# open-race-scale-load-amp.net
KiCad netlist of a schematic drawn in EAGLE
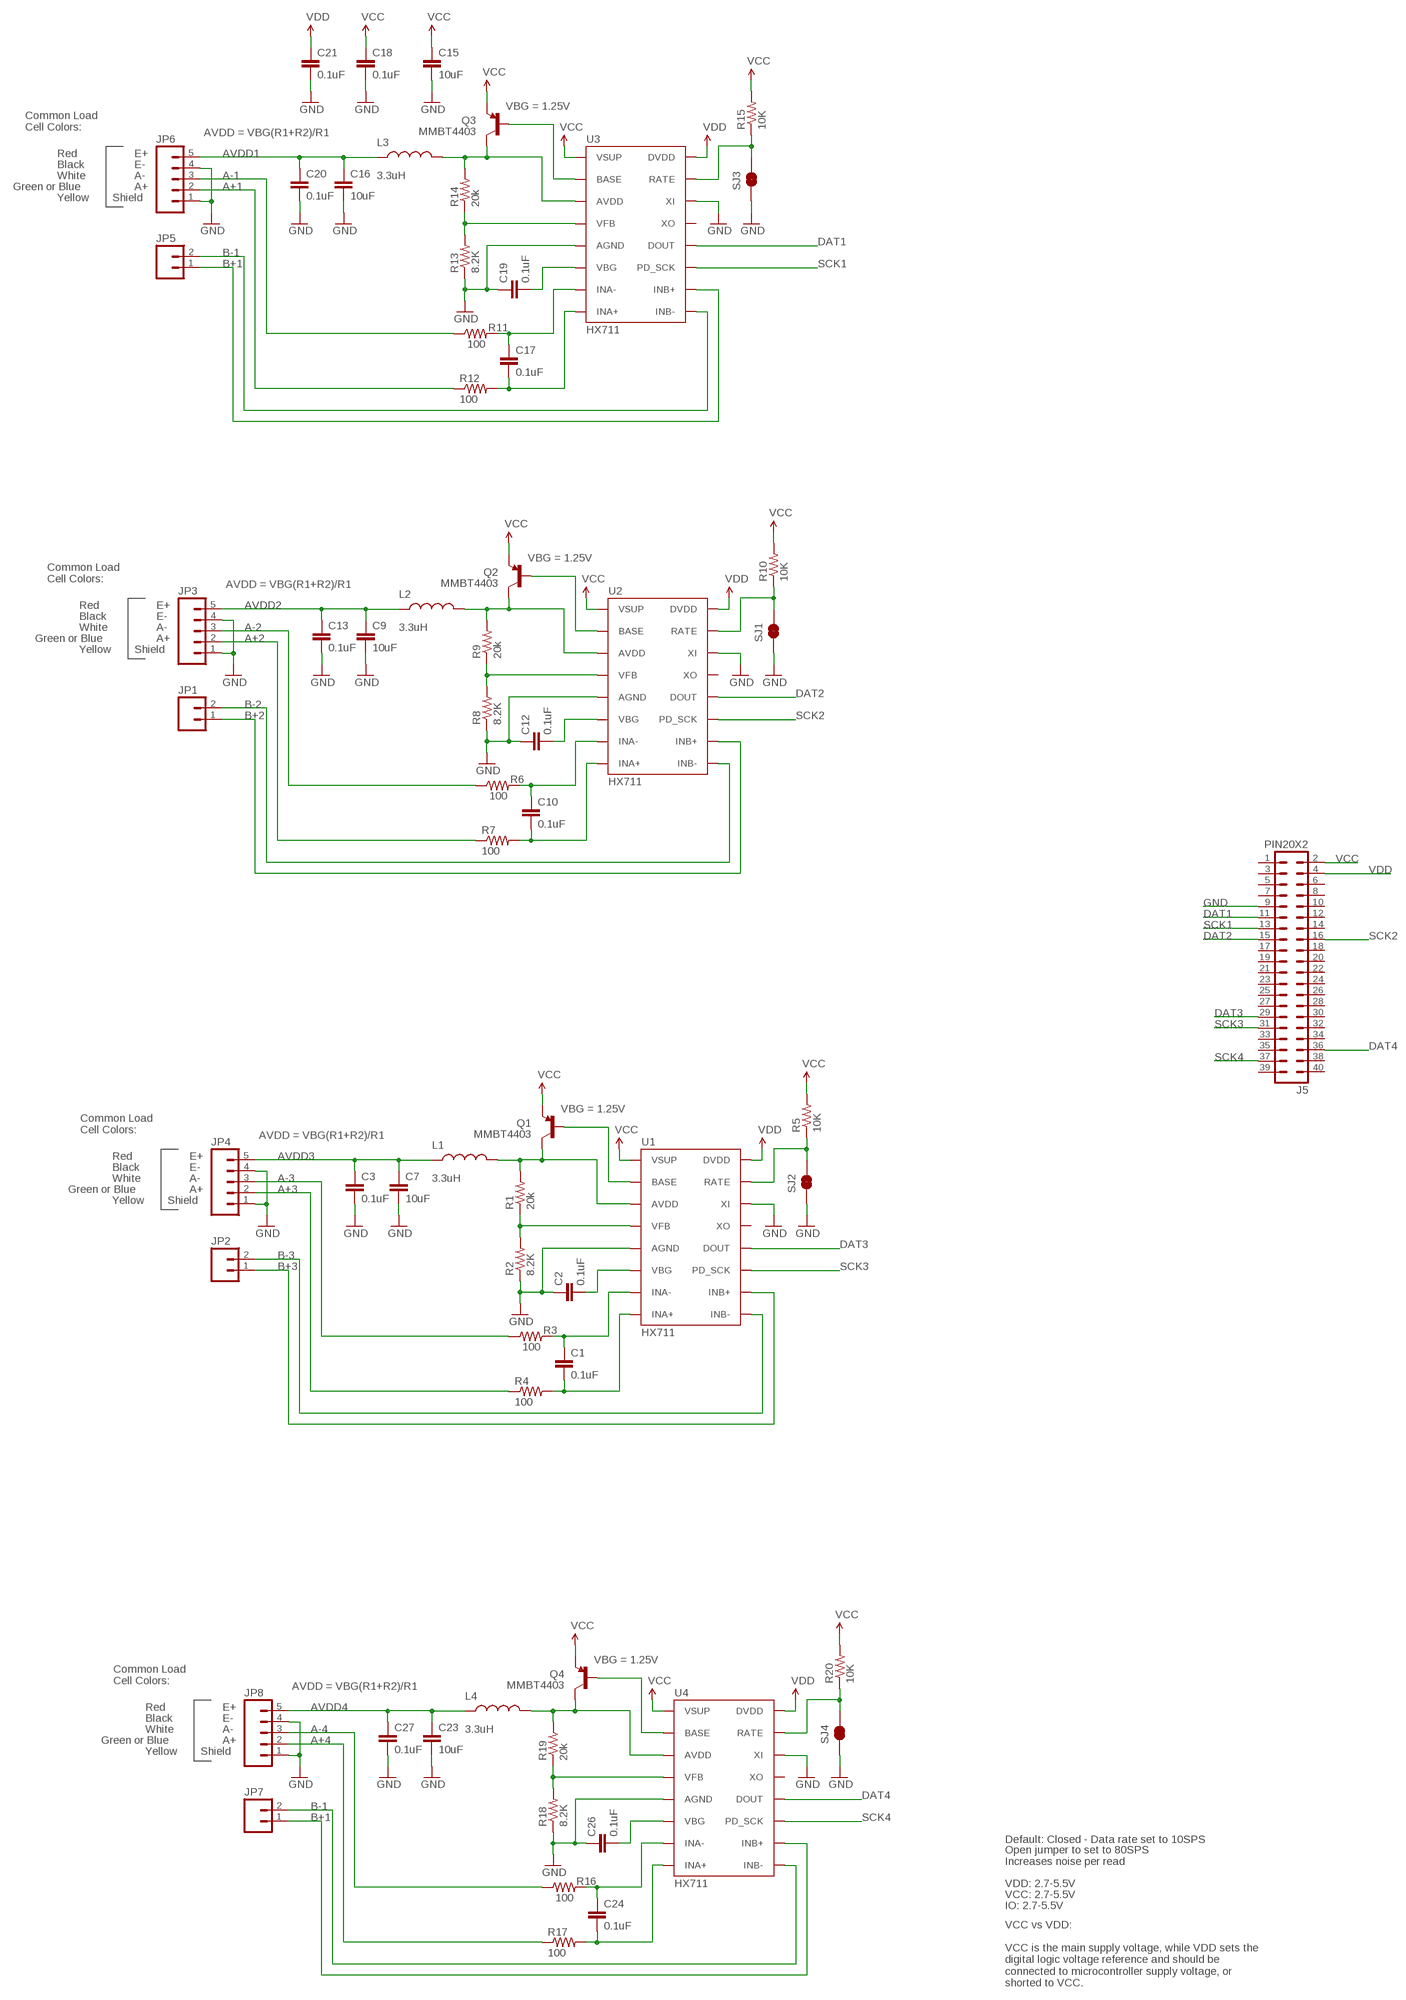
[diagram p0: schematic, sheet 1]

(export (version "E")
  (design (tool "Eeschema 10.0.6"))
  (components
    (comp (ref "C1")
      (value "0.1uF")
      (footprint "eagle-import:0603-CAP")
      (libsource (lib "eagle-import") (part "0.1UF-25V-5%(0603)"))
    )
    (comp (ref "C2")
      (value "0.1uF")
      (footprint "eagle-import:0603-CAP")
      (libsource (lib "eagle-import") (part "0.1UF-25V-5%(0603)"))
    )
    (comp (ref "C3")
      (value "0.1uF")
      (footprint "eagle-import:0603-CAP")
      (libsource (lib "eagle-import") (part "0.1UF-25V-5%(0603)"))
    )
    (comp (ref "C7")
      (value "10uF")
      (footprint "eagle-import:1210")
      (libsource (lib "eagle-import") (part "10UF50V20%(1210)"))
    )
    (comp (ref "C9")
      (value "10uF")
      (footprint "eagle-import:1210")
      (libsource (lib "eagle-import") (part "10UF50V20%(1210)"))
    )
    (comp (ref "C10")
      (value "0.1uF")
      (footprint "eagle-import:0603-CAP")
      (libsource (lib "eagle-import") (part "0.1UF-25V-5%(0603)"))
    )
    (comp (ref "C12")
      (value "0.1uF")
      (footprint "eagle-import:0603-CAP")
      (libsource (lib "eagle-import") (part "0.1UF-25V-5%(0603)"))
    )
    (comp (ref "C13")
      (value "0.1uF")
      (footprint "eagle-import:0603-CAP")
      (libsource (lib "eagle-import") (part "0.1UF-25V-5%(0603)"))
    )
    (comp (ref "C15")
      (value "10uF")
      (footprint "eagle-import:1210")
      (libsource (lib "eagle-import") (part "10UF50V20%(1210)"))
    )
    (comp (ref "C16")
      (value "10uF")
      (footprint "eagle-import:1210")
      (libsource (lib "eagle-import") (part "10UF50V20%(1210)"))
    )
    (comp (ref "C17")
      (value "0.1uF")
      (footprint "eagle-import:0603-CAP")
      (libsource (lib "eagle-import") (part "0.1UF-25V-5%(0603)"))
    )
    (comp (ref "C18")
      (value "0.1uF")
      (footprint "eagle-import:0603-CAP")
      (libsource (lib "eagle-import") (part "0.1UF-25V-5%(0603)"))
    )
    (comp (ref "C19")
      (value "0.1uF")
      (footprint "eagle-import:0603-CAP")
      (libsource (lib "eagle-import") (part "0.1UF-25V-5%(0603)"))
    )
    (comp (ref "C20")
      (value "0.1uF")
      (footprint "eagle-import:0603-CAP")
      (libsource (lib "eagle-import") (part "0.1UF-25V-5%(0603)"))
    )
    (comp (ref "C21")
      (value "0.1uF")
      (footprint "eagle-import:0603-CAP")
      (libsource (lib "eagle-import") (part "0.1UF-25V-5%(0603)"))
    )
    (comp (ref "C23")
      (value "10uF")
      (footprint "eagle-import:1210")
      (libsource (lib "eagle-import") (part "10UF50V20%(1210)"))
    )
    (comp (ref "C24")
      (value "0.1uF")
      (footprint "eagle-import:0603-CAP")
      (libsource (lib "eagle-import") (part "0.1UF-25V-5%(0603)"))
    )
    (comp (ref "C26")
      (value "0.1uF")
      (footprint "eagle-import:0603-CAP")
      (libsource (lib "eagle-import") (part "0.1UF-25V-5%(0603)"))
    )
    (comp (ref "C27")
      (value "0.1uF")
      (footprint "eagle-import:0603-CAP")
      (libsource (lib "eagle-import") (part "0.1UF-25V-5%(0603)"))
    )
    (comp (ref "J5")
      (value "PIN20X2")
      (footprint "eagle-import:PIN_20X2")
      (libsource (lib "eagle-import") (part "PIN20X2"))
    )
    (comp (ref "JP1")
      (value "M02PTH")
      (footprint "eagle-import:1X02")
      (libsource (lib "eagle-import") (part "M02PTH"))
    )
    (comp (ref "JP2")
      (value "M02PTH")
      (footprint "eagle-import:1X02")
      (libsource (lib "eagle-import") (part "M02PTH"))
    )
    (comp (ref "JP3")
      (value "M05PTH")
      (footprint "eagle-import:1X05")
      (libsource (lib "eagle-import") (part "M05PTH"))
    )
    (comp (ref "JP4")
      (value "M05PTH")
      (footprint "eagle-import:1X05")
      (libsource (lib "eagle-import") (part "M05PTH"))
    )
    (comp (ref "JP5")
      (value "M02PTH")
      (footprint "eagle-import:1X02")
      (libsource (lib "eagle-import") (part "M02PTH"))
    )
    (comp (ref "JP6")
      (value "M05PTH")
      (footprint "eagle-import:1X05")
      (libsource (lib "eagle-import") (part "M05PTH"))
    )
    (comp (ref "JP7")
      (value "M02PTH")
      (footprint "eagle-import:1X02")
      (libsource (lib "eagle-import") (part "M02PTH"))
    )
    (comp (ref "JP8")
      (value "M05PTH")
      (footprint "eagle-import:1X05")
      (libsource (lib "eagle-import") (part "M05PTH"))
    )
    (comp (ref "L1")
      (value "3.3uH")
      (footprint "eagle-import:0805")
      (libsource (lib "eagle-import") (part "INDUCTOR0805-IND"))
    )
    (comp (ref "L2")
      (value "3.3uH")
      (footprint "eagle-import:0805")
      (libsource (lib "eagle-import") (part "INDUCTOR0805-IND"))
    )
    (comp (ref "L3")
      (value "3.3uH")
      (footprint "eagle-import:0805")
      (libsource (lib "eagle-import") (part "INDUCTOR0805-IND"))
    )
    (comp (ref "L4")
      (value "3.3uH")
      (footprint "eagle-import:0805")
      (libsource (lib "eagle-import") (part "INDUCTOR0805-IND"))
    )
    (comp (ref "Q1")
      (value "MMBT4403")
      (footprint "eagle-import:SOT23-3")
      (libsource (lib "eagle-import") (part "TRANSISTOR_PNPMMBT4403"))
    )
    (comp (ref "Q2")
      (value "MMBT4403")
      (footprint "eagle-import:SOT23-3")
      (libsource (lib "eagle-import") (part "TRANSISTOR_PNPMMBT4403"))
    )
    (comp (ref "Q3")
      (value "MMBT4403")
      (footprint "eagle-import:SOT23-3")
      (libsource (lib "eagle-import") (part "TRANSISTOR_PNPMMBT4403"))
    )
    (comp (ref "Q4")
      (value "MMBT4403")
      (footprint "eagle-import:SOT23-3")
      (libsource (lib "eagle-import") (part "TRANSISTOR_PNPMMBT4403"))
    )
    (comp (ref "R1")
      (value "20k")
      (footprint "eagle-import:0603-RES")
      (libsource (lib "eagle-import") (part "20KOHM1/10W1%(0603)"))
    )
    (comp (ref "R2")
      (value "8.2K")
      (footprint "eagle-import:0603-RES")
      (libsource (lib "eagle-import") (part "8.2KOHM-1/10W-5%(0603)"))
    )
    (comp (ref "R3")
      (value "100")
      (footprint "eagle-import:0603-RES")
      (libsource (lib "eagle-import") (part "100OHM-1/10W-1%(0603)"))
    )
    (comp (ref "R4")
      (value "100")
      (footprint "eagle-import:0603-RES")
      (libsource (lib "eagle-import") (part "100OHM-1/10W-1%(0603)"))
    )
    (comp (ref "R5")
      (value "10K")
      (footprint "eagle-import:0603-RES")
      (libsource (lib "eagle-import") (part "10KOHM-1/10W-1%(0603)0603"))
    )
    (comp (ref "R6")
      (value "100")
      (footprint "eagle-import:0603-RES")
      (libsource (lib "eagle-import") (part "100OHM-1/10W-1%(0603)"))
    )
    (comp (ref "R7")
      (value "100")
      (footprint "eagle-import:0603-RES")
      (libsource (lib "eagle-import") (part "100OHM-1/10W-1%(0603)"))
    )
    (comp (ref "R8")
      (value "8.2K")
      (footprint "eagle-import:0603-RES")
      (libsource (lib "eagle-import") (part "8.2KOHM-1/10W-5%(0603)"))
    )
    (comp (ref "R9")
      (value "20k")
      (footprint "eagle-import:0603-RES")
      (libsource (lib "eagle-import") (part "20KOHM1/10W1%(0603)"))
    )
    (comp (ref "R10")
      (value "10K")
      (footprint "eagle-import:0603-RES")
      (libsource (lib "eagle-import") (part "10KOHM-1/10W-1%(0603)0603"))
    )
    (comp (ref "R11")
      (value "100")
      (footprint "eagle-import:0603-RES")
      (libsource (lib "eagle-import") (part "100OHM-1/10W-1%(0603)"))
    )
    (comp (ref "R12")
      (value "100")
      (footprint "eagle-import:0603-RES")
      (libsource (lib "eagle-import") (part "100OHM-1/10W-1%(0603)"))
    )
    (comp (ref "R13")
      (value "8.2K")
      (footprint "eagle-import:0603-RES")
      (libsource (lib "eagle-import") (part "8.2KOHM-1/10W-5%(0603)"))
    )
    (comp (ref "R14")
      (value "20k")
      (footprint "eagle-import:0603-RES")
      (libsource (lib "eagle-import") (part "20KOHM1/10W1%(0603)"))
    )
    (comp (ref "R15")
      (value "10K")
      (footprint "eagle-import:0603-RES")
      (libsource (lib "eagle-import") (part "10KOHM-1/10W-1%(0603)0603"))
    )
    (comp (ref "R16")
      (value "100")
      (footprint "eagle-import:0603-RES")
      (libsource (lib "eagle-import") (part "100OHM-1/10W-1%(0603)"))
    )
    (comp (ref "R17")
      (value "100")
      (footprint "eagle-import:0603-RES")
      (libsource (lib "eagle-import") (part "100OHM-1/10W-1%(0603)"))
    )
    (comp (ref "R18")
      (value "8.2K")
      (footprint "eagle-import:0603-RES")
      (libsource (lib "eagle-import") (part "8.2KOHM-1/10W-5%(0603)"))
    )
    (comp (ref "R19")
      (value "20k")
      (footprint "eagle-import:0603-RES")
      (libsource (lib "eagle-import") (part "20KOHM1/10W1%(0603)"))
    )
    (comp (ref "R20")
      (value "10K")
      (footprint "eagle-import:0603-RES")
      (libsource (lib "eagle-import") (part "10KOHM-1/10W-1%(0603)0603"))
    )
    (comp (ref "SJ1")
      (value "JUMPER-PAD-2-NC_BY_TRACE")
      (footprint "eagle-import:PAD-JUMPER-2-NC_BY_TRACE_YES_SILK")
      (libsource (lib "eagle-import") (part "JUMPER-PAD-2-NC_BY_TRACE"))
    )
    (comp (ref "SJ2")
      (value "JUMPER-PAD-2-NC_BY_TRACE")
      (footprint "eagle-import:PAD-JUMPER-2-NC_BY_TRACE_YES_SILK")
      (libsource (lib "eagle-import") (part "JUMPER-PAD-2-NC_BY_TRACE"))
    )
    (comp (ref "SJ3")
      (value "JUMPER-PAD-2-NC_BY_TRACE")
      (footprint "eagle-import:PAD-JUMPER-2-NC_BY_TRACE_YES_SILK")
      (libsource (lib "eagle-import") (part "JUMPER-PAD-2-NC_BY_TRACE"))
    )
    (comp (ref "SJ4")
      (value "JUMPER-PAD-2-NC_BY_TRACE")
      (footprint "eagle-import:PAD-JUMPER-2-NC_BY_TRACE_YES_SILK")
      (libsource (lib "eagle-import") (part "JUMPER-PAD-2-NC_BY_TRACE"))
    )
    (comp (ref "U1")
      (value "HX711")
      (footprint "eagle-import:SO16")
      (libsource (lib "eagle-import") (part "HX711HX711"))
    )
    (comp (ref "U2")
      (value "HX711")
      (footprint "eagle-import:SO16")
      (libsource (lib "eagle-import") (part "HX711HX711"))
    )
    (comp (ref "U3")
      (value "HX711")
      (footprint "eagle-import:SO16")
      (libsource (lib "eagle-import") (part "HX711HX711"))
    )
    (comp (ref "U4")
      (value "HX711")
      (footprint "eagle-import:SO16")
      (libsource (lib "eagle-import") (part "HX711HX711"))
    )
  )
  (nets
    (net (code "1") (name "/A+1") (class "Default")
      (node (ref "JP6") (pin "2") (pinfunction "2_2") (pintype "passive"))
      (node (ref "R12") (pin "1") (pinfunction "1_1") (pintype "passive"))
    )
    (net (code "2") (name "/A+2") (class "Default")
      (node (ref "JP3") (pin "2") (pinfunction "2_2") (pintype "passive"))
      (node (ref "R7") (pin "1") (pinfunction "1_1") (pintype "passive"))
    )
    (net (code "3") (name "/A+3") (class "Default")
      (node (ref "JP4") (pin "2") (pinfunction "2_2") (pintype "passive"))
      (node (ref "R4") (pin "1") (pinfunction "1_1") (pintype "passive"))
    )
    (net (code "4") (name "/A+4") (class "Default")
      (node (ref "JP8") (pin "2") (pinfunction "2_2") (pintype "passive"))
      (node (ref "R17") (pin "1") (pinfunction "1_1") (pintype "passive"))
    )
    (net (code "5") (name "/A-1") (class "Default")
      (node (ref "JP6") (pin "3") (pinfunction "3_3") (pintype "passive"))
      (node (ref "R11") (pin "1") (pinfunction "1_1") (pintype "passive"))
    )
    (net (code "6") (name "/A-2") (class "Default")
      (node (ref "JP3") (pin "3") (pinfunction "3_3") (pintype "passive"))
      (node (ref "R6") (pin "1") (pinfunction "1_1") (pintype "passive"))
    )
    (net (code "7") (name "/A-3") (class "Default")
      (node (ref "JP4") (pin "3") (pinfunction "3_3") (pintype "passive"))
      (node (ref "R3") (pin "1") (pinfunction "1_1") (pintype "passive"))
    )
    (net (code "8") (name "/A-4") (class "Default")
      (node (ref "JP8") (pin "3") (pinfunction "3_3") (pintype "passive"))
      (node (ref "R16") (pin "1") (pinfunction "1_1") (pintype "passive"))
    )
    (net (code "9") (name "/AVDD1") (class "Default")
      (node (ref "C16") (pin "1") (pinfunction "1_1") (pintype "passive"))
      (node (ref "C20") (pin "1") (pinfunction "1_1") (pintype "passive"))
      (node (ref "JP6") (pin "5") (pinfunction "5_5") (pintype "passive"))
      (node (ref "L3") (pin "1") (pinfunction "1_1") (pintype "passive"))
    )
    (net (code "10") (name "/AVDD2") (class "Default")
      (node (ref "C13") (pin "1") (pinfunction "1_1") (pintype "passive"))
      (node (ref "C9") (pin "1") (pinfunction "1_1") (pintype "passive"))
      (node (ref "JP3") (pin "5") (pinfunction "5_5") (pintype "passive"))
      (node (ref "L2") (pin "1") (pinfunction "1_1") (pintype "passive"))
    )
    (net (code "11") (name "/AVDD3") (class "Default")
      (node (ref "C3") (pin "1") (pinfunction "1_1") (pintype "passive"))
      (node (ref "C7") (pin "1") (pinfunction "1_1") (pintype "passive"))
      (node (ref "JP4") (pin "5") (pinfunction "5_5") (pintype "passive"))
      (node (ref "L1") (pin "1") (pinfunction "1_1") (pintype "passive"))
    )
    (net (code "12") (name "/AVDD4") (class "Default")
      (node (ref "C23") (pin "1") (pinfunction "1_1") (pintype "passive"))
      (node (ref "C27") (pin "1") (pinfunction "1_1") (pintype "passive"))
      (node (ref "JP8") (pin "5") (pinfunction "5_5") (pintype "passive"))
      (node (ref "L4") (pin "1") (pinfunction "1_1") (pintype "passive"))
    )
    (net (code "13") (name "/B+1") (class "Default")
      (node (ref "JP5") (pin "1") (pinfunction "1_1") (pintype "passive"))
      (node (ref "JP7") (pin "1") (pinfunction "1_1") (pintype "passive"))
      (node (ref "U3") (pin "10") (pinfunction "INB+_10") (pintype "bidirectional"))
      (node (ref "U4") (pin "10") (pinfunction "INB+_10") (pintype "bidirectional"))
    )
    (net (code "14") (name "/B+2") (class "Default")
      (node (ref "JP1") (pin "1") (pinfunction "1_1") (pintype "passive"))
      (node (ref "U2") (pin "10") (pinfunction "INB+_10") (pintype "bidirectional"))
    )
    (net (code "15") (name "/B+3") (class "Default")
      (node (ref "JP2") (pin "1") (pinfunction "1_1") (pintype "passive"))
      (node (ref "U1") (pin "10") (pinfunction "INB+_10") (pintype "bidirectional"))
    )
    (net (code "16") (name "/B-1") (class "Default")
      (node (ref "JP5") (pin "2") (pinfunction "2_2") (pintype "passive"))
      (node (ref "JP7") (pin "2") (pinfunction "2_2") (pintype "passive"))
      (node (ref "U3") (pin "9") (pinfunction "INB-_9") (pintype "bidirectional"))
      (node (ref "U4") (pin "9") (pinfunction "INB-_9") (pintype "bidirectional"))
    )
    (net (code "17") (name "/B-2") (class "Default")
      (node (ref "JP1") (pin "2") (pinfunction "2_2") (pintype "passive"))
      (node (ref "U2") (pin "9") (pinfunction "INB-_9") (pintype "bidirectional"))
    )
    (net (code "18") (name "/B-3") (class "Default")
      (node (ref "JP2") (pin "2") (pinfunction "2_2") (pintype "passive"))
      (node (ref "U1") (pin "9") (pinfunction "INB-_9") (pintype "bidirectional"))
    )
    (net (code "19") (name "/DAT1") (class "Default")
      (node (ref "J5") (pin "11") (pinfunction "11_11") (pintype "passive"))
      (node (ref "U3") (pin "12") (pinfunction "DOUT_12") (pintype "bidirectional"))
    )
    (net (code "20") (name "/DAT2") (class "Default")
      (node (ref "J5") (pin "15") (pinfunction "15_15") (pintype "passive"))
      (node (ref "U2") (pin "12") (pinfunction "DOUT_12") (pintype "bidirectional"))
    )
    (net (code "21") (name "/DAT3") (class "Default")
      (node (ref "J5") (pin "29") (pinfunction "29_29") (pintype "passive"))
      (node (ref "U1") (pin "12") (pinfunction "DOUT_12") (pintype "bidirectional"))
    )
    (net (code "22") (name "/DAT4") (class "Default")
      (node (ref "J5") (pin "36") (pinfunction "36_36") (pintype "passive"))
      (node (ref "U4") (pin "12") (pinfunction "DOUT_12") (pintype "bidirectional"))
    )
    (net (code "23") (name "/SCK1") (class "Default")
      (node (ref "J5") (pin "13") (pinfunction "13_13") (pintype "passive"))
      (node (ref "U3") (pin "11") (pinfunction "PD_SCK_11") (pintype "bidirectional"))
    )
    (net (code "24") (name "/SCK2") (class "Default")
      (node (ref "J5") (pin "16") (pinfunction "16_16") (pintype "passive"))
      (node (ref "U2") (pin "11") (pinfunction "PD_SCK_11") (pintype "bidirectional"))
    )
    (net (code "25") (name "/SCK3") (class "Default")
      (node (ref "J5") (pin "31") (pinfunction "31_31") (pintype "passive"))
      (node (ref "U1") (pin "11") (pinfunction "PD_SCK_11") (pintype "bidirectional"))
    )
    (net (code "26") (name "/SCK4") (class "Default")
      (node (ref "J5") (pin "37") (pinfunction "37_37") (pintype "passive"))
      (node (ref "U4") (pin "11") (pinfunction "PD_SCK_11") (pintype "bidirectional"))
    )
    (net (code "27") (name "GND") (class "Default")
      (node (ref "C12") (pin "1") (pinfunction "1_1") (pintype "passive"))
      (node (ref "C13") (pin "2") (pinfunction "2_2") (pintype "passive"))
      (node (ref "C15") (pin "2") (pinfunction "2_2") (pintype "passive"))
      (node (ref "C16") (pin "2") (pinfunction "2_2") (pintype "passive"))
      (node (ref "C18") (pin "2") (pinfunction "2_2") (pintype "passive"))
      (node (ref "C19") (pin "1") (pinfunction "1_1") (pintype "passive"))
      (node (ref "C2") (pin "1") (pinfunction "1_1") (pintype "passive"))
      (node (ref "C20") (pin "2") (pinfunction "2_2") (pintype "passive"))
      (node (ref "C21") (pin "2") (pinfunction "2_2") (pintype "passive"))
      (node (ref "C23") (pin "2") (pinfunction "2_2") (pintype "passive"))
      (node (ref "C26") (pin "1") (pinfunction "1_1") (pintype "passive"))
      (node (ref "C27") (pin "2") (pinfunction "2_2") (pintype "passive"))
      (node (ref "C3") (pin "2") (pinfunction "2_2") (pintype "passive"))
      (node (ref "C7") (pin "2") (pinfunction "2_2") (pintype "passive"))
      (node (ref "C9") (pin "2") (pinfunction "2_2") (pintype "passive"))
      (node (ref "J5") (pin "9") (pinfunction "9_9") (pintype "passive"))
      (node (ref "JP3") (pin "1") (pinfunction "1_1") (pintype "passive"))
      (node (ref "JP3") (pin "4") (pinfunction "4_4") (pintype "passive"))
      (node (ref "JP4") (pin "1") (pinfunction "1_1") (pintype "passive"))
      (node (ref "JP4") (pin "4") (pinfunction "4_4") (pintype "passive"))
      (node (ref "JP6") (pin "1") (pinfunction "1_1") (pintype "passive"))
      (node (ref "JP6") (pin "4") (pinfunction "4_4") (pintype "passive"))
      (node (ref "JP8") (pin "1") (pinfunction "1_1") (pintype "passive"))
      (node (ref "JP8") (pin "4") (pinfunction "4_4") (pintype "passive"))
      (node (ref "R13") (pin "1") (pinfunction "1_1") (pintype "passive"))
      (node (ref "R18") (pin "1") (pinfunction "1_1") (pintype "passive"))
      (node (ref "R2") (pin "1") (pinfunction "1_1") (pintype "passive"))
      (node (ref "R8") (pin "1") (pinfunction "1_1") (pintype "passive"))
      (node (ref "SJ1") (pin "1") (pinfunction "1_1") (pintype "passive"))
      (node (ref "SJ2") (pin "1") (pinfunction "1_1") (pintype "passive"))
      (node (ref "SJ3") (pin "1") (pinfunction "1_1") (pintype "passive"))
      (node (ref "SJ4") (pin "1") (pinfunction "1_1") (pintype "passive"))
      (node (ref "U1") (pin "14") (pinfunction "XI_14") (pintype "bidirectional"))
      (node (ref "U1") (pin "5") (pinfunction "AGND_5") (pintype "bidirectional"))
      (node (ref "U2") (pin "14") (pinfunction "XI_14") (pintype "bidirectional"))
      (node (ref "U2") (pin "5") (pinfunction "AGND_5") (pintype "bidirectional"))
      (node (ref "U3") (pin "14") (pinfunction "XI_14") (pintype "bidirectional"))
      (node (ref "U3") (pin "5") (pinfunction "AGND_5") (pintype "bidirectional"))
      (node (ref "U4") (pin "14") (pinfunction "XI_14") (pintype "bidirectional"))
      (node (ref "U4") (pin "5") (pinfunction "AGND_5") (pintype "bidirectional"))
    )
    (net (code "28") (name "Net-(Q1-B)") (class "Default")
      (node (ref "Q1") (pin "1") (pinfunction "B_1") (pintype "passive"))
      (node (ref "U1") (pin "2") (pinfunction "BASE_2") (pintype "bidirectional"))
    )
    (net (code "29") (name "Net-(Q1-C)") (class "Default")
      (node (ref "L1") (pin "2") (pinfunction "2_2") (pintype "passive"))
      (node (ref "Q1") (pin "3") (pinfunction "C_3") (pintype "passive"))
      (node (ref "R1") (pin "2") (pinfunction "2_2") (pintype "passive"))
      (node (ref "U1") (pin "3") (pinfunction "AVDD_3") (pintype "bidirectional"))
    )
    (net (code "30") (name "Net-(Q2-B)") (class "Default")
      (node (ref "Q2") (pin "1") (pinfunction "B_1") (pintype "passive"))
      (node (ref "U2") (pin "2") (pinfunction "BASE_2") (pintype "bidirectional"))
    )
    (net (code "31") (name "Net-(Q2-C)") (class "Default")
      (node (ref "L2") (pin "2") (pinfunction "2_2") (pintype "passive"))
      (node (ref "Q2") (pin "3") (pinfunction "C_3") (pintype "passive"))
      (node (ref "R9") (pin "2") (pinfunction "2_2") (pintype "passive"))
      (node (ref "U2") (pin "3") (pinfunction "AVDD_3") (pintype "bidirectional"))
    )
    (net (code "32") (name "Net-(Q3-B)") (class "Default")
      (node (ref "Q3") (pin "1") (pinfunction "B_1") (pintype "passive"))
      (node (ref "U3") (pin "2") (pinfunction "BASE_2") (pintype "bidirectional"))
    )
    (net (code "33") (name "Net-(Q3-C)") (class "Default")
      (node (ref "L3") (pin "2") (pinfunction "2_2") (pintype "passive"))
      (node (ref "Q3") (pin "3") (pinfunction "C_3") (pintype "passive"))
      (node (ref "R14") (pin "2") (pinfunction "2_2") (pintype "passive"))
      (node (ref "U3") (pin "3") (pinfunction "AVDD_3") (pintype "bidirectional"))
    )
    (net (code "34") (name "Net-(Q4-B)") (class "Default")
      (node (ref "Q4") (pin "1") (pinfunction "B_1") (pintype "passive"))
      (node (ref "U4") (pin "2") (pinfunction "BASE_2") (pintype "bidirectional"))
    )
    (net (code "35") (name "Net-(Q4-C)") (class "Default")
      (node (ref "L4") (pin "2") (pinfunction "2_2") (pintype "passive"))
      (node (ref "Q4") (pin "3") (pinfunction "C_3") (pintype "passive"))
      (node (ref "R19") (pin "2") (pinfunction "2_2") (pintype "passive"))
      (node (ref "U4") (pin "3") (pinfunction "AVDD_3") (pintype "bidirectional"))
    )
    (net (code "36") (name "Net-(U1-INA+)") (class "Default")
      (node (ref "C1") (pin "2") (pinfunction "2_2") (pintype "passive"))
      (node (ref "R4") (pin "2") (pinfunction "2_2") (pintype "passive"))
      (node (ref "U1") (pin "8") (pinfunction "INA+_8") (pintype "bidirectional"))
    )
    (net (code "37") (name "Net-(U1-INA-)") (class "Default")
      (node (ref "C1") (pin "1") (pinfunction "1_1") (pintype "passive"))
      (node (ref "R3") (pin "2") (pinfunction "2_2") (pintype "passive"))
      (node (ref "U1") (pin "7") (pinfunction "INA-_7") (pintype "bidirectional"))
    )
    (net (code "38") (name "Net-(U1-RATE)") (class "Default")
      (node (ref "R5") (pin "1") (pinfunction "1_1") (pintype "passive"))
      (node (ref "SJ2") (pin "2") (pinfunction "2_2") (pintype "passive"))
      (node (ref "U1") (pin "15") (pinfunction "RATE_15") (pintype "bidirectional"))
    )
    (net (code "39") (name "Net-(U1-VBG)") (class "Default")
      (node (ref "C2") (pin "2") (pinfunction "2_2") (pintype "passive"))
      (node (ref "U1") (pin "6") (pinfunction "VBG_6") (pintype "bidirectional"))
    )
    (net (code "40") (name "Net-(U1-VFB)") (class "Default")
      (node (ref "R1") (pin "1") (pinfunction "1_1") (pintype "passive"))
      (node (ref "R2") (pin "2") (pinfunction "2_2") (pintype "passive"))
      (node (ref "U1") (pin "4") (pinfunction "VFB_4") (pintype "bidirectional"))
    )
    (net (code "41") (name "Net-(U2-INA+)") (class "Default")
      (node (ref "C10") (pin "2") (pinfunction "2_2") (pintype "passive"))
      (node (ref "R7") (pin "2") (pinfunction "2_2") (pintype "passive"))
      (node (ref "U2") (pin "8") (pinfunction "INA+_8") (pintype "bidirectional"))
    )
    (net (code "42") (name "Net-(U2-INA-)") (class "Default")
      (node (ref "C10") (pin "1") (pinfunction "1_1") (pintype "passive"))
      (node (ref "R6") (pin "2") (pinfunction "2_2") (pintype "passive"))
      (node (ref "U2") (pin "7") (pinfunction "INA-_7") (pintype "bidirectional"))
    )
    (net (code "43") (name "Net-(U2-RATE)") (class "Default")
      (node (ref "R10") (pin "1") (pinfunction "1_1") (pintype "passive"))
      (node (ref "SJ1") (pin "2") (pinfunction "2_2") (pintype "passive"))
      (node (ref "U2") (pin "15") (pinfunction "RATE_15") (pintype "bidirectional"))
    )
    (net (code "44") (name "Net-(U2-VBG)") (class "Default")
      (node (ref "C12") (pin "2") (pinfunction "2_2") (pintype "passive"))
      (node (ref "U2") (pin "6") (pinfunction "VBG_6") (pintype "bidirectional"))
    )
    (net (code "45") (name "Net-(U2-VFB)") (class "Default")
      (node (ref "R8") (pin "2") (pinfunction "2_2") (pintype "passive"))
      (node (ref "R9") (pin "1") (pinfunction "1_1") (pintype "passive"))
      (node (ref "U2") (pin "4") (pinfunction "VFB_4") (pintype "bidirectional"))
    )
    (net (code "46") (name "Net-(U3-INA+)") (class "Default")
      (node (ref "C17") (pin "2") (pinfunction "2_2") (pintype "passive"))
      (node (ref "R12") (pin "2") (pinfunction "2_2") (pintype "passive"))
      (node (ref "U3") (pin "8") (pinfunction "INA+_8") (pintype "bidirectional"))
    )
    (net (code "47") (name "Net-(U3-INA-)") (class "Default")
      (node (ref "C17") (pin "1") (pinfunction "1_1") (pintype "passive"))
      (node (ref "R11") (pin "2") (pinfunction "2_2") (pintype "passive"))
      (node (ref "U3") (pin "7") (pinfunction "INA-_7") (pintype "bidirectional"))
    )
    (net (code "48") (name "Net-(U3-RATE)") (class "Default")
      (node (ref "R15") (pin "1") (pinfunction "1_1") (pintype "passive"))
      (node (ref "SJ3") (pin "2") (pinfunction "2_2") (pintype "passive"))
      (node (ref "U3") (pin "15") (pinfunction "RATE_15") (pintype "bidirectional"))
    )
    (net (code "49") (name "Net-(U3-VBG)") (class "Default")
      (node (ref "C19") (pin "2") (pinfunction "2_2") (pintype "passive"))
      (node (ref "U3") (pin "6") (pinfunction "VBG_6") (pintype "bidirectional"))
    )
    (net (code "50") (name "Net-(U3-VFB)") (class "Default")
      (node (ref "R13") (pin "2") (pinfunction "2_2") (pintype "passive"))
      (node (ref "R14") (pin "1") (pinfunction "1_1") (pintype "passive"))
      (node (ref "U3") (pin "4") (pinfunction "VFB_4") (pintype "bidirectional"))
    )
    (net (code "51") (name "Net-(U4-INA+)") (class "Default")
      (node (ref "C24") (pin "2") (pinfunction "2_2") (pintype "passive"))
      (node (ref "R17") (pin "2") (pinfunction "2_2") (pintype "passive"))
      (node (ref "U4") (pin "8") (pinfunction "INA+_8") (pintype "bidirectional"))
    )
    (net (code "52") (name "Net-(U4-INA-)") (class "Default")
      (node (ref "C24") (pin "1") (pinfunction "1_1") (pintype "passive"))
      (node (ref "R16") (pin "2") (pinfunction "2_2") (pintype "passive"))
      (node (ref "U4") (pin "7") (pinfunction "INA-_7") (pintype "bidirectional"))
    )
    (net (code "53") (name "Net-(U4-RATE)") (class "Default")
      (node (ref "R20") (pin "1") (pinfunction "1_1") (pintype "passive"))
      (node (ref "SJ4") (pin "2") (pinfunction "2_2") (pintype "passive"))
      (node (ref "U4") (pin "15") (pinfunction "RATE_15") (pintype "bidirectional"))
    )
    (net (code "54") (name "Net-(U4-VBG)") (class "Default")
      (node (ref "C26") (pin "2") (pinfunction "2_2") (pintype "passive"))
      (node (ref "U4") (pin "6") (pinfunction "VBG_6") (pintype "bidirectional"))
    )
    (net (code "55") (name "Net-(U4-VFB)") (class "Default")
      (node (ref "R18") (pin "2") (pinfunction "2_2") (pintype "passive"))
      (node (ref "R19") (pin "1") (pinfunction "1_1") (pintype "passive"))
      (node (ref "U4") (pin "4") (pinfunction "VFB_4") (pintype "bidirectional"))
    )
    (net (code "56") (name "VCC") (class "Default")
      (node (ref "C15") (pin "1") (pinfunction "1_1") (pintype "passive"))
      (node (ref "C18") (pin "1") (pinfunction "1_1") (pintype "passive"))
      (node (ref "J5") (pin "2") (pinfunction "2_2") (pintype "passive"))
      (node (ref "Q1") (pin "2") (pinfunction "E_2") (pintype "passive"))
      (node (ref "Q2") (pin "2") (pinfunction "E_2") (pintype "passive"))
      (node (ref "Q3") (pin "2") (pinfunction "E_2") (pintype "passive"))
      (node (ref "Q4") (pin "2") (pinfunction "E_2") (pintype "passive"))
      (node (ref "R10") (pin "2") (pinfunction "2_2") (pintype "passive"))
      (node (ref "R15") (pin "2") (pinfunction "2_2") (pintype "passive"))
      (node (ref "R20") (pin "2") (pinfunction "2_2") (pintype "passive"))
      (node (ref "R5") (pin "2") (pinfunction "2_2") (pintype "passive"))
      (node (ref "U1") (pin "1") (pinfunction "VSUP_1") (pintype "bidirectional"))
      (node (ref "U2") (pin "1") (pinfunction "VSUP_1") (pintype "bidirectional"))
      (node (ref "U3") (pin "1") (pinfunction "VSUP_1") (pintype "bidirectional"))
      (node (ref "U4") (pin "1") (pinfunction "VSUP_1") (pintype "bidirectional"))
    )
    (net (code "57") (name "VDD") (class "Default")
      (node (ref "C21") (pin "1") (pinfunction "1_1") (pintype "passive"))
      (node (ref "J5") (pin "4") (pinfunction "4_4") (pintype "passive"))
      (node (ref "U1") (pin "16") (pinfunction "DVDD_16") (pintype "bidirectional"))
      (node (ref "U2") (pin "16") (pinfunction "DVDD_16") (pintype "bidirectional"))
      (node (ref "U3") (pin "16") (pinfunction "DVDD_16") (pintype "bidirectional"))
      (node (ref "U4") (pin "16") (pinfunction "DVDD_16") (pintype "bidirectional"))
    )
    (net (code "58") (name "unconnected-(J5-Pad1)") (class "Default")
      (node (ref "J5") (pin "1") (pinfunction "1_1") (pintype "passive"))
    )
    (net (code "59") (name "unconnected-(J5-Pad3)") (class "Default")
      (node (ref "J5") (pin "3") (pinfunction "3_3") (pintype "passive"))
    )
    (net (code "60") (name "unconnected-(J5-Pad5)") (class "Default")
      (node (ref "J5") (pin "5") (pinfunction "5_5") (pintype "passive"))
    )
    (net (code "61") (name "unconnected-(J5-Pad6)") (class "Default")
      (node (ref "J5") (pin "6") (pinfunction "6_6") (pintype "passive"))
    )
    (net (code "62") (name "unconnected-(J5-Pad7)") (class "Default")
      (node (ref "J5") (pin "7") (pinfunction "7_7") (pintype "passive"))
    )
    (net (code "63") (name "unconnected-(J5-Pad8)") (class "Default")
      (node (ref "J5") (pin "8") (pinfunction "8_8") (pintype "passive"))
    )
    (net (code "64") (name "unconnected-(J5-Pad10)") (class "Default")
      (node (ref "J5") (pin "10") (pinfunction "10_10") (pintype "passive"))
    )
    (net (code "65") (name "unconnected-(J5-Pad12)") (class "Default")
      (node (ref "J5") (pin "12") (pinfunction "12_12") (pintype "passive"))
    )
    (net (code "66") (name "unconnected-(J5-Pad14)") (class "Default")
      (node (ref "J5") (pin "14") (pinfunction "14_14") (pintype "passive"))
    )
    (net (code "67") (name "unconnected-(J5-Pad17)") (class "Default")
      (node (ref "J5") (pin "17") (pinfunction "17_17") (pintype "passive"))
    )
    (net (code "68") (name "unconnected-(J5-Pad18)") (class "Default")
      (node (ref "J5") (pin "18") (pinfunction "18_18") (pintype "passive"))
    )
    (net (code "69") (name "unconnected-(J5-Pad19)") (class "Default")
      (node (ref "J5") (pin "19") (pinfunction "19_19") (pintype "passive"))
    )
    (net (code "70") (name "unconnected-(J5-Pad20)") (class "Default")
      (node (ref "J5") (pin "20") (pinfunction "20_20") (pintype "passive"))
    )
    (net (code "71") (name "unconnected-(J5-Pad21)") (class "Default")
      (node (ref "J5") (pin "21") (pinfunction "21_21") (pintype "passive"))
    )
    (net (code "72") (name "unconnected-(J5-Pad22)") (class "Default")
      (node (ref "J5") (pin "22") (pinfunction "22_22") (pintype "passive"))
    )
    (net (code "73") (name "unconnected-(J5-Pad23)") (class "Default")
      (node (ref "J5") (pin "23") (pinfunction "23_23") (pintype "passive"))
    )
    (net (code "74") (name "unconnected-(J5-Pad24)") (class "Default")
      (node (ref "J5") (pin "24") (pinfunction "24_24") (pintype "passive"))
    )
    (net (code "75") (name "unconnected-(J5-Pad25)") (class "Default")
      (node (ref "J5") (pin "25") (pinfunction "25_25") (pintype "passive"))
    )
    (net (code "76") (name "unconnected-(J5-Pad26)") (class "Default")
      (node (ref "J5") (pin "26") (pinfunction "26_26") (pintype "passive"))
    )
    (net (code "77") (name "unconnected-(J5-Pad27)") (class "Default")
      (node (ref "J5") (pin "27") (pinfunction "27_27") (pintype "passive"))
    )
    (net (code "78") (name "unconnected-(J5-Pad28)") (class "Default")
      (node (ref "J5") (pin "28") (pinfunction "28_28") (pintype "passive"))
    )
    (net (code "79") (name "unconnected-(J5-Pad30)") (class "Default")
      (node (ref "J5") (pin "30") (pinfunction "30_30") (pintype "passive"))
    )
    (net (code "80") (name "unconnected-(J5-Pad32)") (class "Default")
      (node (ref "J5") (pin "32") (pinfunction "32_32") (pintype "passive"))
    )
    (net (code "81") (name "unconnected-(J5-Pad33)") (class "Default")
      (node (ref "J5") (pin "33") (pinfunction "33_33") (pintype "passive"))
    )
    (net (code "82") (name "unconnected-(J5-Pad34)") (class "Default")
      (node (ref "J5") (pin "34") (pinfunction "34_34") (pintype "passive"))
    )
    (net (code "83") (name "unconnected-(J5-Pad35)") (class "Default")
      (node (ref "J5") (pin "35") (pinfunction "35_35") (pintype "passive"))
    )
    (net (code "84") (name "unconnected-(J5-Pad38)") (class "Default")
      (node (ref "J5") (pin "38") (pinfunction "38_38") (pintype "passive"))
    )
    (net (code "85") (name "unconnected-(J5-Pad39)") (class "Default")
      (node (ref "J5") (pin "39") (pinfunction "39_39") (pintype "passive"))
    )
    (net (code "86") (name "unconnected-(J5-Pad40)") (class "Default")
      (node (ref "J5") (pin "40") (pinfunction "40_40") (pintype "passive"))
    )
    (net (code "87") (name "unconnected-(U1-XO-Pad13)") (class "Default")
      (node (ref "U1") (pin "13") (pinfunction "XO_13") (pintype "bidirectional"))
    )
    (net (code "88") (name "unconnected-(U2-XO-Pad13)") (class "Default")
      (node (ref "U2") (pin "13") (pinfunction "XO_13") (pintype "bidirectional"))
    )
    (net (code "89") (name "unconnected-(U3-XO-Pad13)") (class "Default")
      (node (ref "U3") (pin "13") (pinfunction "XO_13") (pintype "bidirectional"))
    )
    (net (code "90") (name "unconnected-(U4-XO-Pad13)") (class "Default")
      (node (ref "U4") (pin "13") (pinfunction "XO_13") (pintype "bidirectional"))
    )
  )
)
